# utp_splitter.net
KiCad netlist of a schematic drawn in EAGLE
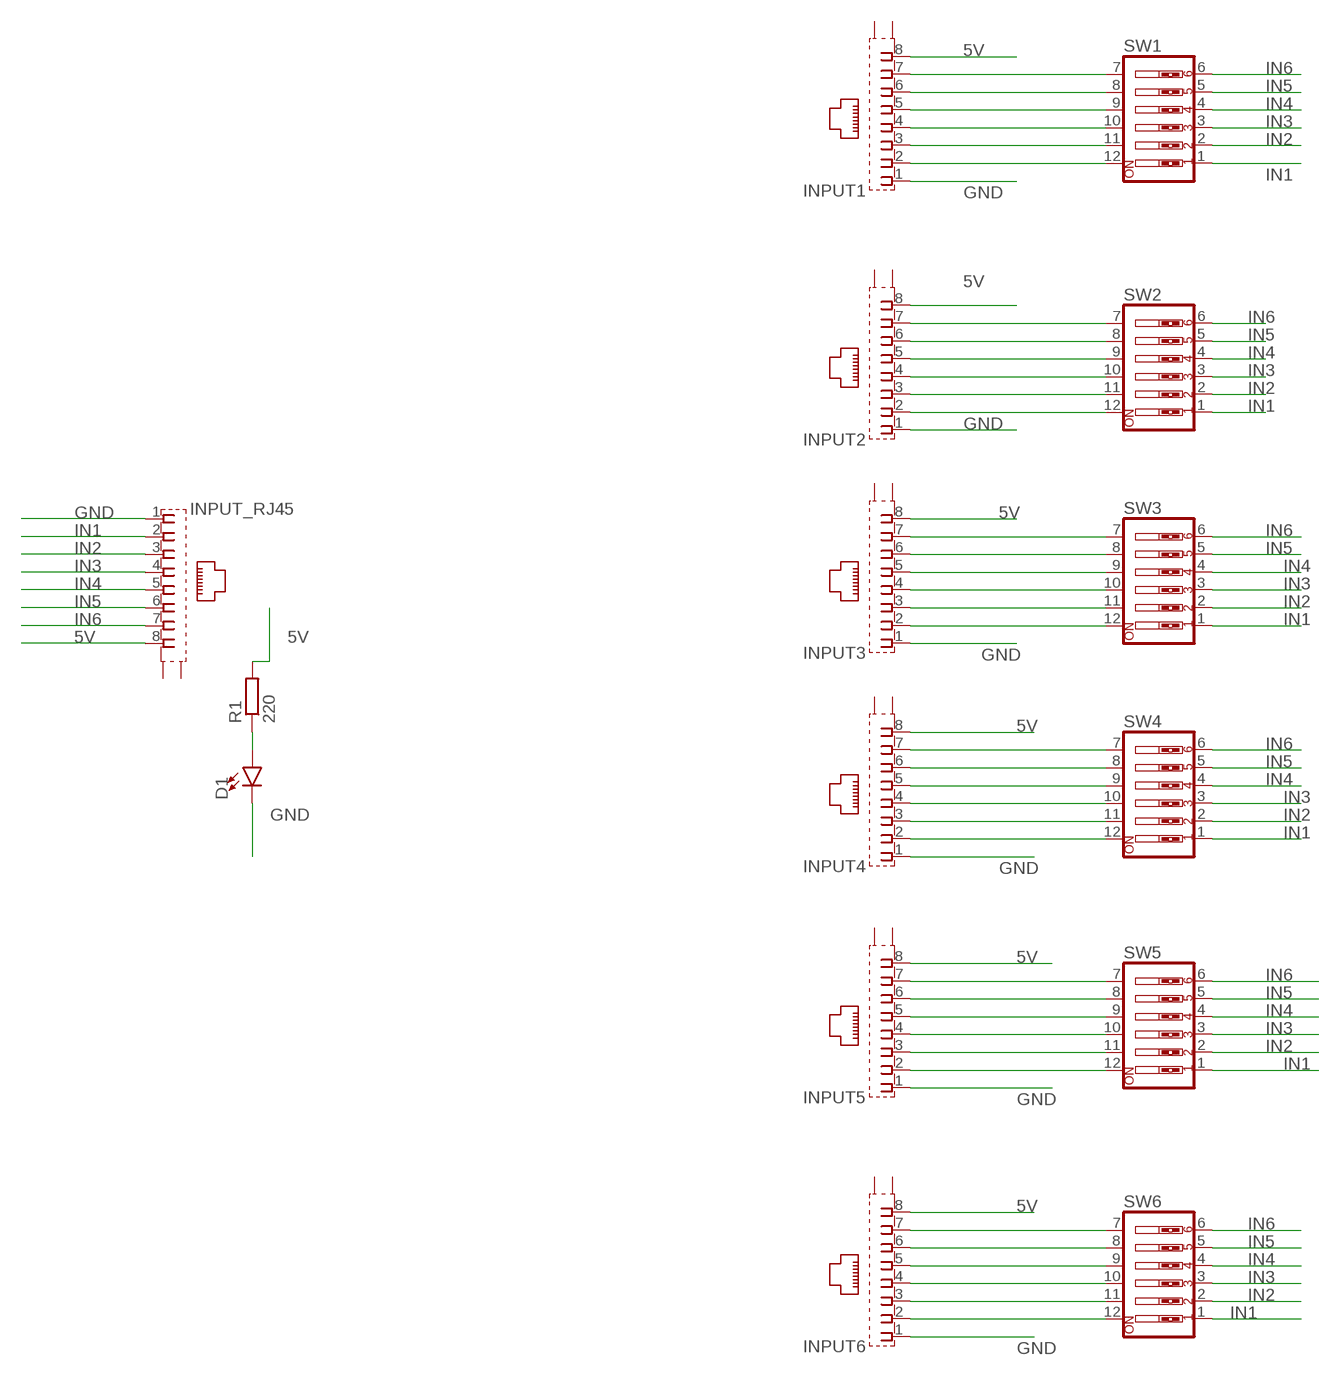
[diagram p0: schematic, sheet 1]

(export (version "E")
  (design (tool "Eeschema 10.0.6"))
  (components
    (comp (ref "D1")
      (value "LED-5MM-KIT-NO-SILK")
      (footprint "eagle-import:LED_5MM-KIT-NO-SILK")
      (libsource (lib "eagle-import") (part "LED-5MM-KIT-NO-SILK"))
    )
    (comp (ref "INPUT1")
      (value "GLX-S-88M")
      (footprint "eagle-import:GLX-S-88M")
      (libsource (lib "eagle-import") (part "GLX-S-88M"))
    )
    (comp (ref "INPUT2")
      (value "GLX-S-88M")
      (footprint "eagle-import:GLX-S-88M")
      (libsource (lib "eagle-import") (part "GLX-S-88M"))
    )
    (comp (ref "INPUT3")
      (value "GLX-S-88M")
      (footprint "eagle-import:GLX-S-88M")
      (libsource (lib "eagle-import") (part "GLX-S-88M"))
    )
    (comp (ref "INPUT4")
      (value "GLX-S-88M")
      (footprint "eagle-import:GLX-S-88M")
      (libsource (lib "eagle-import") (part "GLX-S-88M"))
    )
    (comp (ref "INPUT5")
      (value "GLX-S-88M")
      (footprint "eagle-import:GLX-S-88M")
      (libsource (lib "eagle-import") (part "GLX-S-88M"))
    )
    (comp (ref "INPUT6")
      (value "GLX-S-88M")
      (footprint "eagle-import:GLX-S-88M")
      (libsource (lib "eagle-import") (part "GLX-S-88M"))
    )
    (comp (ref "INPUT_RJ45")
      (value "GLX-S-88M")
      (footprint "eagle-import:GLX-S-88M")
      (libsource (lib "eagle-import") (part "GLX-S-88M"))
    )
    (comp (ref "R1")
      (value "220")
      (footprint "eagle-import:0207_10")
      (libsource (lib "eagle-import") (part "R-EU_0207/10"))
    )
    (comp (ref "SW1")
      (value "SW_DIP-6")
      (footprint "eagle-import:EDG-06")
      (libsource (lib "eagle-import") (part "SW_DIP-6"))
    )
    (comp (ref "SW2")
      (value "SW_DIP-6")
      (footprint "eagle-import:EDG-06")
      (libsource (lib "eagle-import") (part "SW_DIP-6"))
    )
    (comp (ref "SW3")
      (value "SW_DIP-6")
      (footprint "eagle-import:EDG-06")
      (libsource (lib "eagle-import") (part "SW_DIP-6"))
    )
    (comp (ref "SW4")
      (value "SW_DIP-6")
      (footprint "eagle-import:EDG-06")
      (libsource (lib "eagle-import") (part "SW_DIP-6"))
    )
    (comp (ref "SW5")
      (value "SW_DIP-6")
      (footprint "eagle-import:EDG-06")
      (libsource (lib "eagle-import") (part "SW_DIP-6"))
    )
    (comp (ref "SW6")
      (value "SW_DIP-6")
      (footprint "eagle-import:EDG-06")
      (libsource (lib "eagle-import") (part "SW_DIP-6"))
    )
  )
  (nets
    (net (code "1") (name "/5V") (class "Default")
      (node (ref "INPUT1") (pin "8") (pinfunction "8_8") (pintype "passive"))
      (node (ref "INPUT2") (pin "8") (pinfunction "8_8") (pintype "passive"))
      (node (ref "INPUT3") (pin "8") (pinfunction "8_8") (pintype "passive"))
      (node (ref "INPUT4") (pin "8") (pinfunction "8_8") (pintype "passive"))
      (node (ref "INPUT5") (pin "8") (pinfunction "8_8") (pintype "passive"))
      (node (ref "INPUT6") (pin "8") (pinfunction "8_8") (pintype "passive"))
      (node (ref "INPUT_RJ45") (pin "8") (pinfunction "8_8") (pintype "passive"))
      (node (ref "R1") (pin "2") (pinfunction "2_2") (pintype "passive"))
    )
    (net (code "2") (name "/GND") (class "Default")
      (node (ref "D1") (pin "K") (pinfunction "C_K") (pintype "passive"))
      (node (ref "INPUT1") (pin "1") (pinfunction "1_1") (pintype "passive"))
      (node (ref "INPUT2") (pin "1") (pinfunction "1_1") (pintype "passive"))
      (node (ref "INPUT3") (pin "1") (pinfunction "1_1") (pintype "passive"))
      (node (ref "INPUT4") (pin "1") (pinfunction "1_1") (pintype "passive"))
      (node (ref "INPUT5") (pin "1") (pinfunction "1_1") (pintype "passive"))
      (node (ref "INPUT6") (pin "1") (pinfunction "1_1") (pintype "passive"))
      (node (ref "INPUT_RJ45") (pin "1") (pinfunction "1_1") (pintype "passive"))
    )
    (net (code "3") (name "/IN1") (class "Default")
      (node (ref "INPUT_RJ45") (pin "2") (pinfunction "2_2") (pintype "passive"))
      (node (ref "SW1") (pin "1") (pinfunction "1_1") (pintype "passive"))
      (node (ref "SW2") (pin "1") (pinfunction "1_1") (pintype "passive"))
      (node (ref "SW3") (pin "1") (pinfunction "1_1") (pintype "passive"))
      (node (ref "SW4") (pin "1") (pinfunction "1_1") (pintype "passive"))
      (node (ref "SW5") (pin "1") (pinfunction "1_1") (pintype "passive"))
      (node (ref "SW6") (pin "1") (pinfunction "1_1") (pintype "passive"))
    )
    (net (code "4") (name "/IN2") (class "Default")
      (node (ref "INPUT_RJ45") (pin "3") (pinfunction "3_3") (pintype "passive"))
      (node (ref "SW1") (pin "2") (pinfunction "2_2") (pintype "passive"))
      (node (ref "SW2") (pin "2") (pinfunction "2_2") (pintype "passive"))
      (node (ref "SW3") (pin "2") (pinfunction "2_2") (pintype "passive"))
      (node (ref "SW4") (pin "2") (pinfunction "2_2") (pintype "passive"))
      (node (ref "SW5") (pin "2") (pinfunction "2_2") (pintype "passive"))
      (node (ref "SW6") (pin "2") (pinfunction "2_2") (pintype "passive"))
    )
    (net (code "5") (name "/IN3") (class "Default")
      (node (ref "INPUT_RJ45") (pin "4") (pinfunction "4_4") (pintype "passive"))
      (node (ref "SW1") (pin "3") (pinfunction "3_3") (pintype "passive"))
      (node (ref "SW2") (pin "3") (pinfunction "3_3") (pintype "passive"))
      (node (ref "SW3") (pin "3") (pinfunction "3_3") (pintype "passive"))
      (node (ref "SW4") (pin "3") (pinfunction "3_3") (pintype "passive"))
      (node (ref "SW5") (pin "3") (pinfunction "3_3") (pintype "passive"))
      (node (ref "SW6") (pin "3") (pinfunction "3_3") (pintype "passive"))
    )
    (net (code "6") (name "/IN4") (class "Default")
      (node (ref "INPUT_RJ45") (pin "5") (pinfunction "5_5") (pintype "passive"))
      (node (ref "SW1") (pin "4") (pinfunction "4_4") (pintype "passive"))
      (node (ref "SW2") (pin "4") (pinfunction "4_4") (pintype "passive"))
      (node (ref "SW3") (pin "4") (pinfunction "4_4") (pintype "passive"))
      (node (ref "SW4") (pin "4") (pinfunction "4_4") (pintype "passive"))
      (node (ref "SW5") (pin "4") (pinfunction "4_4") (pintype "passive"))
      (node (ref "SW6") (pin "4") (pinfunction "4_4") (pintype "passive"))
    )
    (net (code "7") (name "/IN5") (class "Default")
      (node (ref "INPUT_RJ45") (pin "6") (pinfunction "6_6") (pintype "passive"))
      (node (ref "SW1") (pin "5") (pinfunction "5_5") (pintype "passive"))
      (node (ref "SW2") (pin "5") (pinfunction "5_5") (pintype "passive"))
      (node (ref "SW3") (pin "5") (pinfunction "5_5") (pintype "passive"))
      (node (ref "SW4") (pin "5") (pinfunction "5_5") (pintype "passive"))
      (node (ref "SW5") (pin "5") (pinfunction "5_5") (pintype "passive"))
      (node (ref "SW6") (pin "5") (pinfunction "5_5") (pintype "passive"))
    )
    (net (code "8") (name "/IN6") (class "Default")
      (node (ref "INPUT_RJ45") (pin "7") (pinfunction "7_7") (pintype "passive"))
      (node (ref "SW1") (pin "6") (pinfunction "6_6") (pintype "passive"))
      (node (ref "SW2") (pin "6") (pinfunction "6_6") (pintype "passive"))
      (node (ref "SW3") (pin "6") (pinfunction "6_6") (pintype "passive"))
      (node (ref "SW4") (pin "6") (pinfunction "6_6") (pintype "passive"))
      (node (ref "SW5") (pin "6") (pinfunction "6_6") (pintype "passive"))
      (node (ref "SW6") (pin "6") (pinfunction "6_6") (pintype "passive"))
    )
    (net (code "9") (name "Net-(D1-PadA)") (class "Default")
      (node (ref "D1") (pin "A") (pinfunction "A_A") (pintype "passive"))
      (node (ref "R1") (pin "1") (pinfunction "1_1") (pintype "passive"))
    )
    (net (code "10") (name "Net-(INPUT1-Pad2)") (class "Default")
      (node (ref "INPUT1") (pin "2") (pinfunction "2_2") (pintype "passive"))
      (node (ref "SW1") (pin "12") (pinfunction "12_12") (pintype "passive"))
    )
    (net (code "11") (name "Net-(INPUT1-Pad3)") (class "Default")
      (node (ref "INPUT1") (pin "3") (pinfunction "3_3") (pintype "passive"))
      (node (ref "SW1") (pin "11") (pinfunction "11_11") (pintype "passive"))
    )
    (net (code "12") (name "Net-(INPUT1-Pad4)") (class "Default")
      (node (ref "INPUT1") (pin "4") (pinfunction "4_4") (pintype "passive"))
      (node (ref "SW1") (pin "10") (pinfunction "10_10") (pintype "passive"))
    )
    (net (code "13") (name "Net-(INPUT1-Pad5)") (class "Default")
      (node (ref "INPUT1") (pin "5") (pinfunction "5_5") (pintype "passive"))
      (node (ref "SW1") (pin "9") (pinfunction "9_9") (pintype "passive"))
    )
    (net (code "14") (name "Net-(INPUT1-Pad6)") (class "Default")
      (node (ref "INPUT1") (pin "6") (pinfunction "6_6") (pintype "passive"))
      (node (ref "SW1") (pin "8") (pinfunction "8_8") (pintype "passive"))
    )
    (net (code "15") (name "Net-(INPUT1-Pad7)") (class "Default")
      (node (ref "INPUT1") (pin "7") (pinfunction "7_7") (pintype "passive"))
      (node (ref "SW1") (pin "7") (pinfunction "7_7") (pintype "passive"))
    )
    (net (code "16") (name "Net-(INPUT2-Pad2)") (class "Default")
      (node (ref "INPUT2") (pin "2") (pinfunction "2_2") (pintype "passive"))
      (node (ref "SW2") (pin "12") (pinfunction "12_12") (pintype "passive"))
    )
    (net (code "17") (name "Net-(INPUT2-Pad3)") (class "Default")
      (node (ref "INPUT2") (pin "3") (pinfunction "3_3") (pintype "passive"))
      (node (ref "SW2") (pin "11") (pinfunction "11_11") (pintype "passive"))
    )
    (net (code "18") (name "Net-(INPUT2-Pad4)") (class "Default")
      (node (ref "INPUT2") (pin "4") (pinfunction "4_4") (pintype "passive"))
      (node (ref "SW2") (pin "10") (pinfunction "10_10") (pintype "passive"))
    )
    (net (code "19") (name "Net-(INPUT2-Pad5)") (class "Default")
      (node (ref "INPUT2") (pin "5") (pinfunction "5_5") (pintype "passive"))
      (node (ref "SW2") (pin "9") (pinfunction "9_9") (pintype "passive"))
    )
    (net (code "20") (name "Net-(INPUT2-Pad6)") (class "Default")
      (node (ref "INPUT2") (pin "6") (pinfunction "6_6") (pintype "passive"))
      (node (ref "SW2") (pin "8") (pinfunction "8_8") (pintype "passive"))
    )
    (net (code "21") (name "Net-(INPUT2-Pad7)") (class "Default")
      (node (ref "INPUT2") (pin "7") (pinfunction "7_7") (pintype "passive"))
      (node (ref "SW2") (pin "7") (pinfunction "7_7") (pintype "passive"))
    )
    (net (code "22") (name "Net-(INPUT3-Pad2)") (class "Default")
      (node (ref "INPUT3") (pin "2") (pinfunction "2_2") (pintype "passive"))
      (node (ref "SW3") (pin "12") (pinfunction "12_12") (pintype "passive"))
    )
    (net (code "23") (name "Net-(INPUT3-Pad3)") (class "Default")
      (node (ref "INPUT3") (pin "3") (pinfunction "3_3") (pintype "passive"))
      (node (ref "SW3") (pin "11") (pinfunction "11_11") (pintype "passive"))
    )
    (net (code "24") (name "Net-(INPUT3-Pad4)") (class "Default")
      (node (ref "INPUT3") (pin "4") (pinfunction "4_4") (pintype "passive"))
      (node (ref "SW3") (pin "10") (pinfunction "10_10") (pintype "passive"))
    )
    (net (code "25") (name "Net-(INPUT3-Pad5)") (class "Default")
      (node (ref "INPUT3") (pin "5") (pinfunction "5_5") (pintype "passive"))
      (node (ref "SW3") (pin "9") (pinfunction "9_9") (pintype "passive"))
    )
    (net (code "26") (name "Net-(INPUT3-Pad6)") (class "Default")
      (node (ref "INPUT3") (pin "6") (pinfunction "6_6") (pintype "passive"))
      (node (ref "SW3") (pin "8") (pinfunction "8_8") (pintype "passive"))
    )
    (net (code "27") (name "Net-(INPUT3-Pad7)") (class "Default")
      (node (ref "INPUT3") (pin "7") (pinfunction "7_7") (pintype "passive"))
      (node (ref "SW3") (pin "7") (pinfunction "7_7") (pintype "passive"))
    )
    (net (code "28") (name "Net-(INPUT4-Pad2)") (class "Default")
      (node (ref "INPUT4") (pin "2") (pinfunction "2_2") (pintype "passive"))
      (node (ref "SW4") (pin "12") (pinfunction "12_12") (pintype "passive"))
    )
    (net (code "29") (name "Net-(INPUT4-Pad3)") (class "Default")
      (node (ref "INPUT4") (pin "3") (pinfunction "3_3") (pintype "passive"))
      (node (ref "SW4") (pin "11") (pinfunction "11_11") (pintype "passive"))
    )
    (net (code "30") (name "Net-(INPUT4-Pad4)") (class "Default")
      (node (ref "INPUT4") (pin "4") (pinfunction "4_4") (pintype "passive"))
      (node (ref "SW4") (pin "10") (pinfunction "10_10") (pintype "passive"))
    )
    (net (code "31") (name "Net-(INPUT4-Pad5)") (class "Default")
      (node (ref "INPUT4") (pin "5") (pinfunction "5_5") (pintype "passive"))
      (node (ref "SW4") (pin "9") (pinfunction "9_9") (pintype "passive"))
    )
    (net (code "32") (name "Net-(INPUT4-Pad6)") (class "Default")
      (node (ref "INPUT4") (pin "6") (pinfunction "6_6") (pintype "passive"))
      (node (ref "SW4") (pin "8") (pinfunction "8_8") (pintype "passive"))
    )
    (net (code "33") (name "Net-(INPUT4-Pad7)") (class "Default")
      (node (ref "INPUT4") (pin "7") (pinfunction "7_7") (pintype "passive"))
      (node (ref "SW4") (pin "7") (pinfunction "7_7") (pintype "passive"))
    )
    (net (code "34") (name "Net-(INPUT5-Pad2)") (class "Default")
      (node (ref "INPUT5") (pin "2") (pinfunction "2_2") (pintype "passive"))
      (node (ref "SW5") (pin "12") (pinfunction "12_12") (pintype "passive"))
    )
    (net (code "35") (name "Net-(INPUT5-Pad3)") (class "Default")
      (node (ref "INPUT5") (pin "3") (pinfunction "3_3") (pintype "passive"))
      (node (ref "SW5") (pin "11") (pinfunction "11_11") (pintype "passive"))
    )
    (net (code "36") (name "Net-(INPUT5-Pad4)") (class "Default")
      (node (ref "INPUT5") (pin "4") (pinfunction "4_4") (pintype "passive"))
      (node (ref "SW5") (pin "10") (pinfunction "10_10") (pintype "passive"))
    )
    (net (code "37") (name "Net-(INPUT5-Pad5)") (class "Default")
      (node (ref "INPUT5") (pin "5") (pinfunction "5_5") (pintype "passive"))
      (node (ref "SW5") (pin "9") (pinfunction "9_9") (pintype "passive"))
    )
    (net (code "38") (name "Net-(INPUT5-Pad6)") (class "Default")
      (node (ref "INPUT5") (pin "6") (pinfunction "6_6") (pintype "passive"))
      (node (ref "SW5") (pin "8") (pinfunction "8_8") (pintype "passive"))
    )
    (net (code "39") (name "Net-(INPUT5-Pad7)") (class "Default")
      (node (ref "INPUT5") (pin "7") (pinfunction "7_7") (pintype "passive"))
      (node (ref "SW5") (pin "7") (pinfunction "7_7") (pintype "passive"))
    )
    (net (code "40") (name "Net-(INPUT6-Pad2)") (class "Default")
      (node (ref "INPUT6") (pin "2") (pinfunction "2_2") (pintype "passive"))
      (node (ref "SW6") (pin "12") (pinfunction "12_12") (pintype "passive"))
    )
    (net (code "41") (name "Net-(INPUT6-Pad3)") (class "Default")
      (node (ref "INPUT6") (pin "3") (pinfunction "3_3") (pintype "passive"))
      (node (ref "SW6") (pin "11") (pinfunction "11_11") (pintype "passive"))
    )
    (net (code "42") (name "Net-(INPUT6-Pad4)") (class "Default")
      (node (ref "INPUT6") (pin "4") (pinfunction "4_4") (pintype "passive"))
      (node (ref "SW6") (pin "10") (pinfunction "10_10") (pintype "passive"))
    )
    (net (code "43") (name "Net-(INPUT6-Pad5)") (class "Default")
      (node (ref "INPUT6") (pin "5") (pinfunction "5_5") (pintype "passive"))
      (node (ref "SW6") (pin "9") (pinfunction "9_9") (pintype "passive"))
    )
    (net (code "44") (name "Net-(INPUT6-Pad6)") (class "Default")
      (node (ref "INPUT6") (pin "6") (pinfunction "6_6") (pintype "passive"))
      (node (ref "SW6") (pin "8") (pinfunction "8_8") (pintype "passive"))
    )
    (net (code "45") (name "Net-(INPUT6-Pad7)") (class "Default")
      (node (ref "INPUT6") (pin "7") (pinfunction "7_7") (pintype "passive"))
      (node (ref "SW6") (pin "7") (pinfunction "7_7") (pintype "passive"))
    )
    (net (code "46") (name "unconnected-(INPUT1-PadS1)") (class "Default")
      (node (ref "INPUT1") (pin "S1") (pinfunction "S1_S1") (pintype "passive"))
    )
    (net (code "47") (name "unconnected-(INPUT1-PadS2)") (class "Default")
      (node (ref "INPUT1") (pin "S2") (pinfunction "S2_S2") (pintype "passive"))
    )
    (net (code "48") (name "unconnected-(INPUT2-PadS1)") (class "Default")
      (node (ref "INPUT2") (pin "S1") (pinfunction "S1_S1") (pintype "passive"))
    )
    (net (code "49") (name "unconnected-(INPUT2-PadS2)") (class "Default")
      (node (ref "INPUT2") (pin "S2") (pinfunction "S2_S2") (pintype "passive"))
    )
    (net (code "50") (name "unconnected-(INPUT3-PadS1)") (class "Default")
      (node (ref "INPUT3") (pin "S1") (pinfunction "S1_S1") (pintype "passive"))
    )
    (net (code "51") (name "unconnected-(INPUT3-PadS2)") (class "Default")
      (node (ref "INPUT3") (pin "S2") (pinfunction "S2_S2") (pintype "passive"))
    )
    (net (code "52") (name "unconnected-(INPUT4-PadS1)") (class "Default")
      (node (ref "INPUT4") (pin "S1") (pinfunction "S1_S1") (pintype "passive"))
    )
    (net (code "53") (name "unconnected-(INPUT4-PadS2)") (class "Default")
      (node (ref "INPUT4") (pin "S2") (pinfunction "S2_S2") (pintype "passive"))
    )
    (net (code "54") (name "unconnected-(INPUT5-PadS1)") (class "Default")
      (node (ref "INPUT5") (pin "S1") (pinfunction "S1_S1") (pintype "passive"))
    )
    (net (code "55") (name "unconnected-(INPUT5-PadS2)") (class "Default")
      (node (ref "INPUT5") (pin "S2") (pinfunction "S2_S2") (pintype "passive"))
    )
    (net (code "56") (name "unconnected-(INPUT6-PadS1)") (class "Default")
      (node (ref "INPUT6") (pin "S1") (pinfunction "S1_S1") (pintype "passive"))
    )
    (net (code "57") (name "unconnected-(INPUT6-PadS2)") (class "Default")
      (node (ref "INPUT6") (pin "S2") (pinfunction "S2_S2") (pintype "passive"))
    )
    (net (code "58") (name "unconnected-(INPUT_RJ45-PadS1)") (class "Default")
      (node (ref "INPUT_RJ45") (pin "S1") (pinfunction "S1_S1") (pintype "passive"))
    )
    (net (code "59") (name "unconnected-(INPUT_RJ45-PadS2)") (class "Default")
      (node (ref "INPUT_RJ45") (pin "S2") (pinfunction "S2_S2") (pintype "passive"))
    )
  )
)
